# unit_module.net
KiCad netlist of a schematic drawn in EAGLE
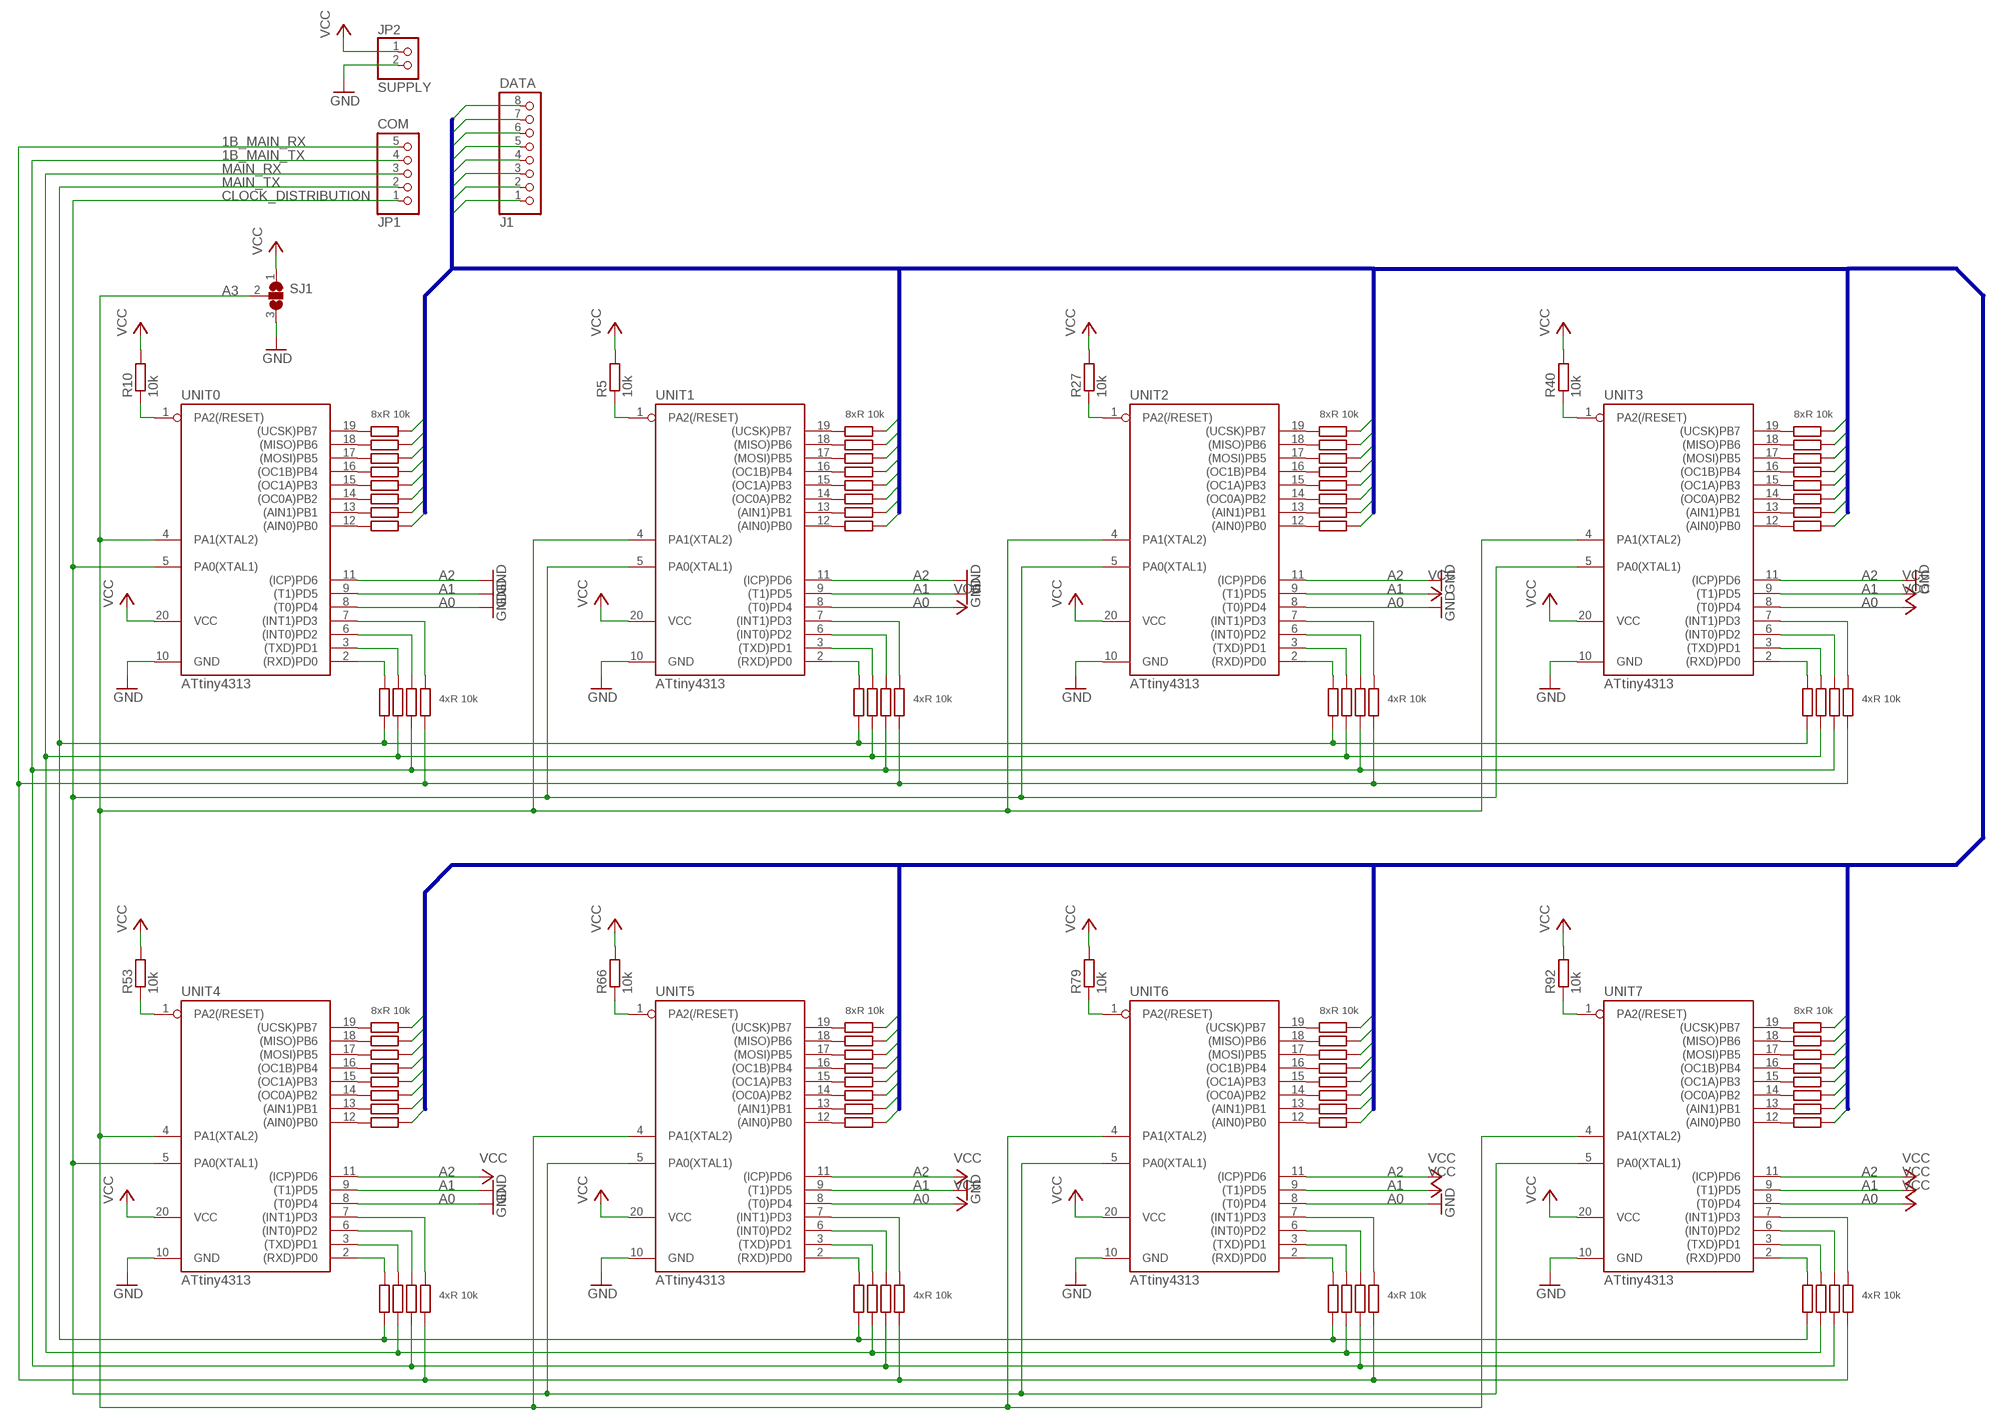
[diagram p0: schematic, sheet 1]

(export (version "E")
  (design (tool "Eeschema 10.0.6"))
  (components
    (comp (ref "J1")
      (value "DATA")
      (footprint "eagle-import:1X08")
      (libsource (lib "eagle-import") (part "PINHD-1X8"))
    )
    (comp (ref "JP1")
      (value "COM")
      (footprint "eagle-import:1X05")
      (libsource (lib "eagle-import") (part "PINHD-1X5"))
    )
    (comp (ref "JP2")
      (value "SUPPLY")
      (footprint "eagle-import:1X02")
      (libsource (lib "eagle-import") (part "PINHD-1X2"))
    )
    (comp (ref "R1")
      (value "10k")
      (footprint "eagle-import:R0603")
      (libsource (lib "eagle-import") (part "R-EU_R0603"))
    )
    (comp (ref "R2")
      (value "10k")
      (footprint "eagle-import:R0603")
      (libsource (lib "eagle-import") (part "R-EU_R0603"))
    )
    (comp (ref "R3")
      (value "10k")
      (footprint "eagle-import:R0603")
      (libsource (lib "eagle-import") (part "R-EU_R0603"))
    )
    (comp (ref "R4")
      (value "10k")
      (footprint "eagle-import:R0603")
      (libsource (lib "eagle-import") (part "R-EU_R0603"))
    )
    (comp (ref "R5")
      (value "10k")
      (footprint "eagle-import:R0603")
      (libsource (lib "eagle-import") (part "R-EU_R0603"))
    )
    (comp (ref "R6")
      (value "10k")
      (footprint "eagle-import:R0603")
      (libsource (lib "eagle-import") (part "R-EU_R0603"))
    )
    (comp (ref "R7")
      (value "10k")
      (footprint "eagle-import:R0603")
      (libsource (lib "eagle-import") (part "R-EU_R0603"))
    )
    (comp (ref "R8")
      (value "10k")
      (footprint "eagle-import:R0603")
      (libsource (lib "eagle-import") (part "R-EU_R0603"))
    )
    (comp (ref "R9")
      (value "10k")
      (footprint "eagle-import:R0603")
      (libsource (lib "eagle-import") (part "R-EU_R0603"))
    )
    (comp (ref "R10")
      (value "10k")
      (footprint "eagle-import:R0603")
      (libsource (lib "eagle-import") (part "R-EU_R0603"))
    )
    (comp (ref "R11")
      (value "10k")
      (footprint "eagle-import:R0603")
      (libsource (lib "eagle-import") (part "R-EU_R0603"))
    )
    (comp (ref "R12")
      (value "10k")
      (footprint "eagle-import:R0603")
      (libsource (lib "eagle-import") (part "R-EU_R0603"))
    )
    (comp (ref "R13")
      (value "10k")
      (footprint "eagle-import:R0603")
      (libsource (lib "eagle-import") (part "R-EU_R0603"))
    )
    (comp (ref "R14")
      (value "10k")
      (footprint "eagle-import:R0603")
      (libsource (lib "eagle-import") (part "R-EU_R0603"))
    )
    (comp (ref "R15")
      (value "10k")
      (footprint "eagle-import:R0603")
      (libsource (lib "eagle-import") (part "R-EU_R0603"))
    )
    (comp (ref "R16")
      (value "10k")
      (footprint "eagle-import:R0603")
      (libsource (lib "eagle-import") (part "R-EU_R0603"))
    )
    (comp (ref "R17")
      (value "10k")
      (footprint "eagle-import:R0603")
      (libsource (lib "eagle-import") (part "R-EU_R0603"))
    )
    (comp (ref "R18")
      (value "10k")
      (footprint "eagle-import:R0603")
      (libsource (lib "eagle-import") (part "R-EU_R0603"))
    )
    (comp (ref "R19")
      (value "10k")
      (footprint "eagle-import:R0603")
      (libsource (lib "eagle-import") (part "R-EU_R0603"))
    )
    (comp (ref "R20")
      (value "10k")
      (footprint "eagle-import:R0603")
      (libsource (lib "eagle-import") (part "R-EU_R0603"))
    )
    (comp (ref "R21")
      (value "10k")
      (footprint "eagle-import:R0603")
      (libsource (lib "eagle-import") (part "R-EU_R0603"))
    )
    (comp (ref "R22")
      (value "10k")
      (footprint "eagle-import:R0603")
      (libsource (lib "eagle-import") (part "R-EU_R0603"))
    )
    (comp (ref "R23")
      (value "10k")
      (footprint "eagle-import:R0603")
      (libsource (lib "eagle-import") (part "R-EU_R0603"))
    )
    (comp (ref "R24")
      (value "10k")
      (footprint "eagle-import:R0603")
      (libsource (lib "eagle-import") (part "R-EU_R0603"))
    )
    (comp (ref "R25")
      (value "10k")
      (footprint "eagle-import:R0603")
      (libsource (lib "eagle-import") (part "R-EU_R0603"))
    )
    (comp (ref "R26")
      (value "10k")
      (footprint "eagle-import:R0603")
      (libsource (lib "eagle-import") (part "R-EU_R0603"))
    )
    (comp (ref "R27")
      (value "10k")
      (footprint "eagle-import:R0603")
      (libsource (lib "eagle-import") (part "R-EU_R0603"))
    )
    (comp (ref "R28")
      (value "10k")
      (footprint "eagle-import:R0603")
      (libsource (lib "eagle-import") (part "R-EU_R0603"))
    )
    (comp (ref "R29")
      (value "10k")
      (footprint "eagle-import:R0603")
      (libsource (lib "eagle-import") (part "R-EU_R0603"))
    )
    (comp (ref "R30")
      (value "10k")
      (footprint "eagle-import:R0603")
      (libsource (lib "eagle-import") (part "R-EU_R0603"))
    )
    (comp (ref "R31")
      (value "10k")
      (footprint "eagle-import:R0603")
      (libsource (lib "eagle-import") (part "R-EU_R0603"))
    )
    (comp (ref "R32")
      (value "10k")
      (footprint "eagle-import:R0603")
      (libsource (lib "eagle-import") (part "R-EU_R0603"))
    )
    (comp (ref "R33")
      (value "10k")
      (footprint "eagle-import:R0603")
      (libsource (lib "eagle-import") (part "R-EU_R0603"))
    )
    (comp (ref "R34")
      (value "10k")
      (footprint "eagle-import:R0603")
      (libsource (lib "eagle-import") (part "R-EU_R0603"))
    )
    (comp (ref "R35")
      (value "10k")
      (footprint "eagle-import:R0603")
      (libsource (lib "eagle-import") (part "R-EU_R0603"))
    )
    (comp (ref "R36")
      (value "10k")
      (footprint "eagle-import:R0603")
      (libsource (lib "eagle-import") (part "R-EU_R0603"))
    )
    (comp (ref "R37")
      (value "10k")
      (footprint "eagle-import:R0603")
      (libsource (lib "eagle-import") (part "R-EU_R0603"))
    )
    (comp (ref "R38")
      (value "10k")
      (footprint "eagle-import:R0603")
      (libsource (lib "eagle-import") (part "R-EU_R0603"))
    )
    (comp (ref "R39")
      (value "10k")
      (footprint "eagle-import:R0603")
      (libsource (lib "eagle-import") (part "R-EU_R0603"))
    )
    (comp (ref "R40")
      (value "10k")
      (footprint "eagle-import:R0603")
      (libsource (lib "eagle-import") (part "R-EU_R0603"))
    )
    (comp (ref "R41")
      (value "10k")
      (footprint "eagle-import:R0603")
      (libsource (lib "eagle-import") (part "R-EU_R0603"))
    )
    (comp (ref "R42")
      (value "10k")
      (footprint "eagle-import:R0603")
      (libsource (lib "eagle-import") (part "R-EU_R0603"))
    )
    (comp (ref "R43")
      (value "10k")
      (footprint "eagle-import:R0603")
      (libsource (lib "eagle-import") (part "R-EU_R0603"))
    )
    (comp (ref "R44")
      (value "10k")
      (footprint "eagle-import:R0603")
      (libsource (lib "eagle-import") (part "R-EU_R0603"))
    )
    (comp (ref "R45")
      (value "10k")
      (footprint "eagle-import:R0603")
      (libsource (lib "eagle-import") (part "R-EU_R0603"))
    )
    (comp (ref "R46")
      (value "10k")
      (footprint "eagle-import:R0603")
      (libsource (lib "eagle-import") (part "R-EU_R0603"))
    )
    (comp (ref "R47")
      (value "10k")
      (footprint "eagle-import:R0603")
      (libsource (lib "eagle-import") (part "R-EU_R0603"))
    )
    (comp (ref "R48")
      (value "10k")
      (footprint "eagle-import:R0603")
      (libsource (lib "eagle-import") (part "R-EU_R0603"))
    )
    (comp (ref "R49")
      (value "10k")
      (footprint "eagle-import:R0603")
      (libsource (lib "eagle-import") (part "R-EU_R0603"))
    )
    (comp (ref "R50")
      (value "10k")
      (footprint "eagle-import:R0603")
      (libsource (lib "eagle-import") (part "R-EU_R0603"))
    )
    (comp (ref "R51")
      (value "10k")
      (footprint "eagle-import:R0603")
      (libsource (lib "eagle-import") (part "R-EU_R0603"))
    )
    (comp (ref "R52")
      (value "10k")
      (footprint "eagle-import:R0603")
      (libsource (lib "eagle-import") (part "R-EU_R0603"))
    )
    (comp (ref "R53")
      (value "10k")
      (footprint "eagle-import:R0603")
      (libsource (lib "eagle-import") (part "R-EU_R0603"))
    )
    (comp (ref "R54")
      (value "10k")
      (footprint "eagle-import:R0603")
      (libsource (lib "eagle-import") (part "R-EU_R0603"))
    )
    (comp (ref "R55")
      (value "10k")
      (footprint "eagle-import:R0603")
      (libsource (lib "eagle-import") (part "R-EU_R0603"))
    )
    (comp (ref "R56")
      (value "10k")
      (footprint "eagle-import:R0603")
      (libsource (lib "eagle-import") (part "R-EU_R0603"))
    )
    (comp (ref "R57")
      (value "10k")
      (footprint "eagle-import:R0603")
      (libsource (lib "eagle-import") (part "R-EU_R0603"))
    )
    (comp (ref "R58")
      (value "10k")
      (footprint "eagle-import:R0603")
      (libsource (lib "eagle-import") (part "R-EU_R0603"))
    )
    (comp (ref "R59")
      (value "10k")
      (footprint "eagle-import:R0603")
      (libsource (lib "eagle-import") (part "R-EU_R0603"))
    )
    (comp (ref "R60")
      (value "10k")
      (footprint "eagle-import:R0603")
      (libsource (lib "eagle-import") (part "R-EU_R0603"))
    )
    (comp (ref "R61")
      (value "10k")
      (footprint "eagle-import:R0603")
      (libsource (lib "eagle-import") (part "R-EU_R0603"))
    )
    (comp (ref "R62")
      (value "10k")
      (footprint "eagle-import:R0603")
      (libsource (lib "eagle-import") (part "R-EU_R0603"))
    )
    (comp (ref "R63")
      (value "10k")
      (footprint "eagle-import:R0603")
      (libsource (lib "eagle-import") (part "R-EU_R0603"))
    )
    (comp (ref "R64")
      (value "10k")
      (footprint "eagle-import:R0603")
      (libsource (lib "eagle-import") (part "R-EU_R0603"))
    )
    (comp (ref "R65")
      (value "10k")
      (footprint "eagle-import:R0603")
      (libsource (lib "eagle-import") (part "R-EU_R0603"))
    )
    (comp (ref "R66")
      (value "10k")
      (footprint "eagle-import:R0603")
      (libsource (lib "eagle-import") (part "R-EU_R0603"))
    )
    (comp (ref "R67")
      (value "10k")
      (footprint "eagle-import:R0603")
      (libsource (lib "eagle-import") (part "R-EU_R0603"))
    )
    (comp (ref "R68")
      (value "10k")
      (footprint "eagle-import:R0603")
      (libsource (lib "eagle-import") (part "R-EU_R0603"))
    )
    (comp (ref "R69")
      (value "10k")
      (footprint "eagle-import:R0603")
      (libsource (lib "eagle-import") (part "R-EU_R0603"))
    )
    (comp (ref "R70")
      (value "10k")
      (footprint "eagle-import:R0603")
      (libsource (lib "eagle-import") (part "R-EU_R0603"))
    )
    (comp (ref "R71")
      (value "10k")
      (footprint "eagle-import:R0603")
      (libsource (lib "eagle-import") (part "R-EU_R0603"))
    )
    (comp (ref "R72")
      (value "10k")
      (footprint "eagle-import:R0603")
      (libsource (lib "eagle-import") (part "R-EU_R0603"))
    )
    (comp (ref "R73")
      (value "10k")
      (footprint "eagle-import:R0603")
      (libsource (lib "eagle-import") (part "R-EU_R0603"))
    )
    (comp (ref "R74")
      (value "10k")
      (footprint "eagle-import:R0603")
      (libsource (lib "eagle-import") (part "R-EU_R0603"))
    )
    (comp (ref "R75")
      (value "10k")
      (footprint "eagle-import:R0603")
      (libsource (lib "eagle-import") (part "R-EU_R0603"))
    )
    (comp (ref "R76")
      (value "10k")
      (footprint "eagle-import:R0603")
      (libsource (lib "eagle-import") (part "R-EU_R0603"))
    )
    (comp (ref "R77")
      (value "10k")
      (footprint "eagle-import:R0603")
      (libsource (lib "eagle-import") (part "R-EU_R0603"))
    )
    (comp (ref "R78")
      (value "10k")
      (footprint "eagle-import:R0603")
      (libsource (lib "eagle-import") (part "R-EU_R0603"))
    )
    (comp (ref "R79")
      (value "10k")
      (footprint "eagle-import:R0603")
      (libsource (lib "eagle-import") (part "R-EU_R0603"))
    )
    (comp (ref "R80")
      (value "10k")
      (footprint "eagle-import:R0603")
      (libsource (lib "eagle-import") (part "R-EU_R0603"))
    )
    (comp (ref "R81")
      (value "10k")
      (footprint "eagle-import:R0603")
      (libsource (lib "eagle-import") (part "R-EU_R0603"))
    )
    (comp (ref "R82")
      (value "10k")
      (footprint "eagle-import:R0603")
      (libsource (lib "eagle-import") (part "R-EU_R0603"))
    )
    (comp (ref "R83")
      (value "10k")
      (footprint "eagle-import:R0603")
      (libsource (lib "eagle-import") (part "R-EU_R0603"))
    )
    (comp (ref "R84")
      (value "10k")
      (footprint "eagle-import:R0603")
      (libsource (lib "eagle-import") (part "R-EU_R0603"))
    )
    (comp (ref "R85")
      (value "10k")
      (footprint "eagle-import:R0603")
      (libsource (lib "eagle-import") (part "R-EU_R0603"))
    )
    (comp (ref "R86")
      (value "10k")
      (footprint "eagle-import:R0603")
      (libsource (lib "eagle-import") (part "R-EU_R0603"))
    )
    (comp (ref "R87")
      (value "10k")
      (footprint "eagle-import:R0603")
      (libsource (lib "eagle-import") (part "R-EU_R0603"))
    )
    (comp (ref "R88")
      (value "10k")
      (footprint "eagle-import:R0603")
      (libsource (lib "eagle-import") (part "R-EU_R0603"))
    )
    (comp (ref "R89")
      (value "10k")
      (footprint "eagle-import:R0603")
      (libsource (lib "eagle-import") (part "R-EU_R0603"))
    )
    (comp (ref "R90")
      (value "10k")
      (footprint "eagle-import:R0603")
      (libsource (lib "eagle-import") (part "R-EU_R0603"))
    )
    (comp (ref "R91")
      (value "10k")
      (footprint "eagle-import:R0603")
      (libsource (lib "eagle-import") (part "R-EU_R0603"))
    )
    (comp (ref "R92")
      (value "10k")
      (footprint "eagle-import:R0603")
      (libsource (lib "eagle-import") (part "R-EU_R0603"))
    )
    (comp (ref "R93")
      (value "10k")
      (footprint "eagle-import:R0603")
      (libsource (lib "eagle-import") (part "R-EU_R0603"))
    )
    (comp (ref "R94")
      (value "10k")
      (footprint "eagle-import:R0603")
      (libsource (lib "eagle-import") (part "R-EU_R0603"))
    )
    (comp (ref "R95")
      (value "10k")
      (footprint "eagle-import:R0603")
      (libsource (lib "eagle-import") (part "R-EU_R0603"))
    )
    (comp (ref "R96")
      (value "10k")
      (footprint "eagle-import:R0603")
      (libsource (lib "eagle-import") (part "R-EU_R0603"))
    )
    (comp (ref "R97")
      (value "10k")
      (footprint "eagle-import:R0603")
      (libsource (lib "eagle-import") (part "R-EU_R0603"))
    )
    (comp (ref "R98")
      (value "10k")
      (footprint "eagle-import:R0603")
      (libsource (lib "eagle-import") (part "R-EU_R0603"))
    )
    (comp (ref "R99")
      (value "10k")
      (footprint "eagle-import:R0603")
      (libsource (lib "eagle-import") (part "R-EU_R0603"))
    )
    (comp (ref "R100")
      (value "10k")
      (footprint "eagle-import:R0603")
      (libsource (lib "eagle-import") (part "R-EU_R0603"))
    )
    (comp (ref "R101")
      (value "10k")
      (footprint "eagle-import:R0603")
      (libsource (lib "eagle-import") (part "R-EU_R0603"))
    )
    (comp (ref "R102")
      (value "10k")
      (footprint "eagle-import:R0603")
      (libsource (lib "eagle-import") (part "R-EU_R0603"))
    )
    (comp (ref "R103")
      (value "10k")
      (footprint "eagle-import:R0603")
      (libsource (lib "eagle-import") (part "R-EU_R0603"))
    )
    (comp (ref "R104")
      (value "10k")
      (footprint "eagle-import:R0603")
      (libsource (lib "eagle-import") (part "R-EU_R0603"))
    )
    (comp (ref "SJ1")
      (value "SJ2W")
      (footprint "eagle-import:SJ_2")
      (libsource (lib "eagle-import") (part "SJ2W"))
    )
    (comp (ref "UNIT0")
      (value "ATtiny4313")
      (footprint "eagle-import:DIL20")
      (libsource (lib "eagle-import") (part "TINY2313-P"))
    )
    (comp (ref "UNIT1")
      (value "ATtiny4313")
      (footprint "eagle-import:DIL20")
      (libsource (lib "eagle-import") (part "TINY2313-P"))
    )
    (comp (ref "UNIT2")
      (value "ATtiny4313")
      (footprint "eagle-import:DIL20")
      (libsource (lib "eagle-import") (part "TINY2313-P"))
    )
    (comp (ref "UNIT3")
      (value "ATtiny4313")
      (footprint "eagle-import:DIL20")
      (libsource (lib "eagle-import") (part "TINY2313-P"))
    )
    (comp (ref "UNIT4")
      (value "ATtiny4313")
      (footprint "eagle-import:DIL20")
      (libsource (lib "eagle-import") (part "TINY2313-P"))
    )
    (comp (ref "UNIT5")
      (value "ATtiny4313")
      (footprint "eagle-import:DIL20")
      (libsource (lib "eagle-import") (part "TINY2313-P"))
    )
    (comp (ref "UNIT6")
      (value "ATtiny4313")
      (footprint "eagle-import:DIL20")
      (libsource (lib "eagle-import") (part "TINY2313-P"))
    )
    (comp (ref "UNIT7")
      (value "ATtiny4313")
      (footprint "eagle-import:DIL20")
      (libsource (lib "eagle-import") (part "TINY2313-P"))
    )
  )
  (nets
    (net (code "1") (name "/1B_MAIN_RX") (class "Default")
      (node (ref "JP1") (pin "5") (pinfunction "5_5") (pintype "passive"))
      (node (ref "R104") (pin "2") (pinfunction "2_2") (pintype "passive"))
      (node (ref "R26") (pin "2") (pinfunction "2_2") (pintype "passive"))
      (node (ref "R39") (pin "2") (pinfunction "2_2") (pintype "passive"))
      (node (ref "R4") (pin "2") (pinfunction "2_2") (pintype "passive"))
      (node (ref "R52") (pin "2") (pinfunction "2_2") (pintype "passive"))
      (node (ref "R65") (pin "2") (pinfunction "2_2") (pintype "passive"))
      (node (ref "R78") (pin "2") (pinfunction "2_2") (pintype "passive"))
      (node (ref "R91") (pin "2") (pinfunction "2_2") (pintype "passive"))
    )
    (net (code "2") (name "/1B_MAIN_TX") (class "Default")
      (node (ref "JP1") (pin "4") (pinfunction "4_4") (pintype "passive"))
      (node (ref "R103") (pin "2") (pinfunction "2_2") (pintype "passive"))
      (node (ref "R25") (pin "2") (pinfunction "2_2") (pintype "passive"))
      (node (ref "R3") (pin "2") (pinfunction "2_2") (pintype "passive"))
      (node (ref "R38") (pin "2") (pinfunction "2_2") (pintype "passive"))
      (node (ref "R51") (pin "2") (pinfunction "2_2") (pintype "passive"))
      (node (ref "R64") (pin "2") (pinfunction "2_2") (pintype "passive"))
      (node (ref "R77") (pin "2") (pinfunction "2_2") (pintype "passive"))
      (node (ref "R90") (pin "2") (pinfunction "2_2") (pintype "passive"))
    )
    (net (code "3") (name "/A3") (class "Default")
      (node (ref "SJ1") (pin "2") (pinfunction "2_2") (pintype "passive"))
      (node (ref "UNIT0") (pin "4") (pinfunction "PA1(XTAL2)_4") (pintype "bidirectional"))
      (node (ref "UNIT1") (pin "4") (pinfunction "PA1(XTAL2)_4") (pintype "bidirectional"))
      (node (ref "UNIT2") (pin "4") (pinfunction "PA1(XTAL2)_4") (pintype "bidirectional"))
      (node (ref "UNIT3") (pin "4") (pinfunction "PA1(XTAL2)_4") (pintype "bidirectional"))
      (node (ref "UNIT4") (pin "4") (pinfunction "PA1(XTAL2)_4") (pintype "bidirectional"))
      (node (ref "UNIT5") (pin "4") (pinfunction "PA1(XTAL2)_4") (pintype "bidirectional"))
      (node (ref "UNIT6") (pin "4") (pinfunction "PA1(XTAL2)_4") (pintype "bidirectional"))
      (node (ref "UNIT7") (pin "4") (pinfunction "PA1(XTAL2)_4") (pintype "bidirectional"))
    )
    (net (code "4") (name "/CLOCK_DISTRIBUTION") (class "Default")
      (node (ref "JP1") (pin "1") (pinfunction "1_1") (pintype "passive"))
      (node (ref "UNIT0") (pin "5") (pinfunction "PA0(XTAL1)_5") (pintype "bidirectional"))
      (node (ref "UNIT1") (pin "5") (pinfunction "PA0(XTAL1)_5") (pintype "bidirectional"))
      (node (ref "UNIT2") (pin "5") (pinfunction "PA0(XTAL1)_5") (pintype "bidirectional"))
      (node (ref "UNIT3") (pin "5") (pinfunction "PA0(XTAL1)_5") (pintype "bidirectional"))
      (node (ref "UNIT4") (pin "5") (pinfunction "PA0(XTAL1)_5") (pintype "bidirectional"))
      (node (ref "UNIT5") (pin "5") (pinfunction "PA0(XTAL1)_5") (pintype "bidirectional"))
      (node (ref "UNIT6") (pin "5") (pinfunction "PA0(XTAL1)_5") (pintype "bidirectional"))
      (node (ref "UNIT7") (pin "5") (pinfunction "PA0(XTAL1)_5") (pintype "bidirectional"))
    )
    (net (code "5") (name "/DATA0") (class "Default")
      (node (ref "J1") (pin "1") (pinfunction "1_1") (pintype "passive"))
      (node (ref "R100") (pin "1") (pinfunction "1_1") (pintype "passive"))
      (node (ref "R19") (pin "1") (pinfunction "1_1") (pintype "passive"))
      (node (ref "R22") (pin "1") (pinfunction "1_1") (pintype "passive"))
      (node (ref "R35") (pin "1") (pinfunction "1_1") (pintype "passive"))
      (node (ref "R48") (pin "1") (pinfunction "1_1") (pintype "passive"))
      (node (ref "R61") (pin "1") (pinfunction "1_1") (pintype "passive"))
      (node (ref "R74") (pin "1") (pinfunction "1_1") (pintype "passive"))
      (node (ref "R87") (pin "1") (pinfunction "1_1") (pintype "passive"))
    )
    (net (code "6") (name "/DATA1") (class "Default")
      (node (ref "J1") (pin "2") (pinfunction "2_2") (pintype "passive"))
      (node (ref "R18") (pin "1") (pinfunction "1_1") (pintype "passive"))
      (node (ref "R21") (pin "1") (pinfunction "1_1") (pintype "passive"))
      (node (ref "R34") (pin "1") (pinfunction "1_1") (pintype "passive"))
      (node (ref "R47") (pin "1") (pinfunction "1_1") (pintype "passive"))
      (node (ref "R60") (pin "1") (pinfunction "1_1") (pintype "passive"))
      (node (ref "R73") (pin "1") (pinfunction "1_1") (pintype "passive"))
      (node (ref "R86") (pin "1") (pinfunction "1_1") (pintype "passive"))
      (node (ref "R99") (pin "1") (pinfunction "1_1") (pintype "passive"))
    )
    (net (code "7") (name "/DATA2") (class "Default")
      (node (ref "J1") (pin "3") (pinfunction "3_3") (pintype "passive"))
      (node (ref "R17") (pin "1") (pinfunction "1_1") (pintype "passive"))
      (node (ref "R20") (pin "1") (pinfunction "1_1") (pintype "passive"))
      (node (ref "R33") (pin "1") (pinfunction "1_1") (pintype "passive"))
      (node (ref "R46") (pin "1") (pinfunction "1_1") (pintype "passive"))
      (node (ref "R59") (pin "1") (pinfunction "1_1") (pintype "passive"))
      (node (ref "R72") (pin "1") (pinfunction "1_1") (pintype "passive"))
      (node (ref "R85") (pin "1") (pinfunction "1_1") (pintype "passive"))
      (node (ref "R98") (pin "1") (pinfunction "1_1") (pintype "passive"))
    )
    (net (code "8") (name "/DATA3") (class "Default")
      (node (ref "J1") (pin "4") (pinfunction "4_4") (pintype "passive"))
      (node (ref "R11") (pin "1") (pinfunction "1_1") (pintype "passive"))
      (node (ref "R16") (pin "1") (pinfunction "1_1") (pintype "passive"))
      (node (ref "R32") (pin "1") (pinfunction "1_1") (pintype "passive"))
      (node (ref "R45") (pin "1") (pinfunction "1_1") (pintype "passive"))
      (node (ref "R58") (pin "1") (pinfunction "1_1") (pintype "passive"))
      (node (ref "R71") (pin "1") (pinfunction "1_1") (pintype "passive"))
      (node (ref "R84") (pin "1") (pinfunction "1_1") (pintype "passive"))
      (node (ref "R97") (pin "1") (pinfunction "1_1") (pintype "passive"))
    )
    (net (code "9") (name "/DATA4") (class "Default")
      (node (ref "J1") (pin "5") (pinfunction "5_5") (pintype "passive"))
      (node (ref "R15") (pin "1") (pinfunction "1_1") (pintype "passive"))
      (node (ref "R31") (pin "1") (pinfunction "1_1") (pintype "passive"))
      (node (ref "R44") (pin "1") (pinfunction "1_1") (pintype "passive"))
      (node (ref "R57") (pin "1") (pinfunction "1_1") (pintype "passive"))
      (node (ref "R70") (pin "1") (pinfunction "1_1") (pintype "passive"))
      (node (ref "R83") (pin "1") (pinfunction "1_1") (pintype "passive"))
      (node (ref "R9") (pin "1") (pinfunction "1_1") (pintype "passive"))
      (node (ref "R96") (pin "1") (pinfunction "1_1") (pintype "passive"))
    )
    (net (code "10") (name "/DATA5") (class "Default")
      (node (ref "J1") (pin "6") (pinfunction "6_6") (pintype "passive"))
      (node (ref "R14") (pin "1") (pinfunction "1_1") (pintype "passive"))
      (node (ref "R30") (pin "1") (pinfunction "1_1") (pintype "passive"))
      (node (ref "R43") (pin "1") (pinfunction "1_1") (pintype "passive"))
      (node (ref "R56") (pin "1") (pinfunction "1_1") (pintype "passive"))
      (node (ref "R69") (pin "1") (pinfunction "1_1") (pintype "passive"))
      (node (ref "R8") (pin "1") (pinfunction "1_1") (pintype "passive"))
      (node (ref "R82") (pin "1") (pinfunction "1_1") (pintype "passive"))
      (node (ref "R95") (pin "1") (pinfunction "1_1") (pintype "passive"))
    )
    (net (code "11") (name "/DATA6") (class "Default")
      (node (ref "J1") (pin "7") (pinfunction "7_7") (pintype "passive"))
      (node (ref "R13") (pin "1") (pinfunction "1_1") (pintype "passive"))
      (node (ref "R29") (pin "1") (pinfunction "1_1") (pintype "passive"))
      (node (ref "R42") (pin "1") (pinfunction "1_1") (pintype "passive"))
      (node (ref "R55") (pin "1") (pinfunction "1_1") (pintype "passive"))
      (node (ref "R68") (pin "1") (pinfunction "1_1") (pintype "passive"))
      (node (ref "R7") (pin "1") (pinfunction "1_1") (pintype "passive"))
      (node (ref "R81") (pin "1") (pinfunction "1_1") (pintype "passive"))
      (node (ref "R94") (pin "1") (pinfunction "1_1") (pintype "passive"))
    )
    (net (code "12") (name "/DATA7") (class "Default")
      (node (ref "J1") (pin "8") (pinfunction "8_8") (pintype "passive"))
      (node (ref "R12") (pin "1") (pinfunction "1_1") (pintype "passive"))
      (node (ref "R28") (pin "1") (pinfunction "1_1") (pintype "passive"))
      (node (ref "R41") (pin "1") (pinfunction "1_1") (pintype "passive"))
      (node (ref "R54") (pin "1") (pinfunction "1_1") (pintype "passive"))
      (node (ref "R6") (pin "1") (pinfunction "1_1") (pintype "passive"))
      (node (ref "R67") (pin "1") (pinfunction "1_1") (pintype "passive"))
      (node (ref "R80") (pin "1") (pinfunction "1_1") (pintype "passive"))
      (node (ref "R93") (pin "1") (pinfunction "1_1") (pintype "passive"))
    )
    (net (code "13") (name "/MAIN_RX") (class "Default")
      (node (ref "JP1") (pin "3") (pinfunction "3_3") (pintype "passive"))
      (node (ref "R102") (pin "2") (pinfunction "2_2") (pintype "passive"))
      (node (ref "R2") (pin "2") (pinfunction "2_2") (pintype "passive"))
      (node (ref "R24") (pin "2") (pinfunction "2_2") (pintype "passive"))
      (node (ref "R37") (pin "2") (pinfunction "2_2") (pintype "passive"))
      (node (ref "R50") (pin "2") (pinfunction "2_2") (pintype "passive"))
      (node (ref "R63") (pin "2") (pinfunction "2_2") (pintype "passive"))
      (node (ref "R76") (pin "2") (pinfunction "2_2") (pintype "passive"))
      (node (ref "R89") (pin "2") (pinfunction "2_2") (pintype "passive"))
    )
    (net (code "14") (name "/MAIN_TX") (class "Default")
      (node (ref "JP1") (pin "2") (pinfunction "2_2") (pintype "passive"))
      (node (ref "R1") (pin "2") (pinfunction "2_2") (pintype "passive"))
      (node (ref "R101") (pin "2") (pinfunction "2_2") (pintype "passive"))
      (node (ref "R23") (pin "2") (pinfunction "2_2") (pintype "passive"))
      (node (ref "R36") (pin "2") (pinfunction "2_2") (pintype "passive"))
      (node (ref "R49") (pin "2") (pinfunction "2_2") (pintype "passive"))
      (node (ref "R62") (pin "2") (pinfunction "2_2") (pintype "passive"))
      (node (ref "R75") (pin "2") (pinfunction "2_2") (pintype "passive"))
      (node (ref "R88") (pin "2") (pinfunction "2_2") (pintype "passive"))
    )
    (net (code "15") (name "GND") (class "Default")
      (node (ref "JP2") (pin "2") (pinfunction "2_2") (pintype "passive"))
      (node (ref "SJ1") (pin "3") (pinfunction "3_3") (pintype "passive"))
      (node (ref "UNIT0") (pin "10") (pinfunction "GND_10") (pintype "power_in"))
      (node (ref "UNIT0") (pin "11") (pinfunction "(ICP)PD6_11") (pintype "bidirectional"))
      (node (ref "UNIT0") (pin "8") (pinfunction "(T0)PD4_8") (pintype "bidirectional"))
      (node (ref "UNIT0") (pin "9") (pinfunction "(T1)PD5_9") (pintype "bidirectional"))
      (node (ref "UNIT1") (pin "10") (pinfunction "GND_10") (pintype "power_in"))
      (node (ref "UNIT1") (pin "11") (pinfunction "(ICP)PD6_11") (pintype "bidirectional"))
      (node (ref "UNIT1") (pin "9") (pinfunction "(T1)PD5_9") (pintype "bidirectional"))
      (node (ref "UNIT2") (pin "10") (pinfunction "GND_10") (pintype "power_in"))
      (node (ref "UNIT2") (pin "11") (pinfunction "(ICP)PD6_11") (pintype "bidirectional"))
      (node (ref "UNIT2") (pin "8") (pinfunction "(T0)PD4_8") (pintype "bidirectional"))
      (node (ref "UNIT3") (pin "10") (pinfunction "GND_10") (pintype "power_in"))
      (node (ref "UNIT3") (pin "11") (pinfunction "(ICP)PD6_11") (pintype "bidirectional"))
      (node (ref "UNIT4") (pin "10") (pinfunction "GND_10") (pintype "power_in"))
      (node (ref "UNIT4") (pin "8") (pinfunction "(T0)PD4_8") (pintype "bidirectional"))
      (node (ref "UNIT4") (pin "9") (pinfunction "(T1)PD5_9") (pintype "bidirectional"))
      (node (ref "UNIT5") (pin "10") (pinfunction "GND_10") (pintype "power_in"))
      (node (ref "UNIT5") (pin "9") (pinfunction "(T1)PD5_9") (pintype "bidirectional"))
      (node (ref "UNIT6") (pin "10") (pinfunction "GND_10") (pintype "power_in"))
      (node (ref "UNIT6") (pin "8") (pinfunction "(T0)PD4_8") (pintype "bidirectional"))
      (node (ref "UNIT7") (pin "10") (pinfunction "GND_10") (pintype "power_in"))
    )
    (net (code "16") (name "Net-(UNIT0-(AIN0)PB0)") (class "Default")
      (node (ref "R19") (pin "2") (pinfunction "2_2") (pintype "passive"))
      (node (ref "UNIT0") (pin "12") (pinfunction "(AIN0)PB0_12") (pintype "bidirectional"))
    )
    (net (code "17") (name "Net-(UNIT0-(AIN1)PB1)") (class "Default")
      (node (ref "R18") (pin "2") (pinfunction "2_2") (pintype "passive"))
      (node (ref "UNIT0") (pin "13") (pinfunction "(AIN1)PB1_13") (pintype "bidirectional"))
    )
    (net (code "18") (name "Net-(UNIT0-(INT0)PD2)") (class "Default")
      (node (ref "R3") (pin "1") (pinfunction "1_1") (pintype "passive"))
      (node (ref "UNIT0") (pin "6") (pinfunction "(INT0)PD2_6") (pintype "bidirectional"))
    )
    (net (code "19") (name "Net-(UNIT0-(INT1)PD3)") (class "Default")
      (node (ref "R4") (pin "1") (pinfunction "1_1") (pintype "passive"))
      (node (ref "UNIT0") (pin "7") (pinfunction "(INT1)PD3_7") (pintype "bidirectional"))
    )
    (net (code "20") (name "Net-(UNIT0-(MISO)PB6)") (class "Default")
      (node (ref "R13") (pin "2") (pinfunction "2_2") (pintype "passive"))
      (node (ref "UNIT0") (pin "18") (pinfunction "(MISO)PB6_18") (pintype "bidirectional"))
    )
    (net (code "21") (name "Net-(UNIT0-(MOSI)PB5)") (class "Default")
      (node (ref "R14") (pin "2") (pinfunction "2_2") (pintype "passive"))
      (node (ref "UNIT0") (pin "17") (pinfunction "(MOSI)PB5_17") (pintype "bidirectional"))
    )
    (net (code "22") (name "Net-(UNIT0-(OC0A)PB2)") (class "Default")
      (node (ref "R17") (pin "2") (pinfunction "2_2") (pintype "passive"))
      (node (ref "UNIT0") (pin "14") (pinfunction "(OC0A)PB2_14") (pintype "bidirectional"))
    )
    (net (code "23") (name "Net-(UNIT0-(OC1A)PB3)") (class "Default")
      (node (ref "R16") (pin "2") (pinfunction "2_2") (pintype "passive"))
      (node (ref "UNIT0") (pin "15") (pinfunction "(OC1A)PB3_15") (pintype "bidirectional"))
    )
    (net (code "24") (name "Net-(UNIT0-(OC1B)PB4)") (class "Default")
      (node (ref "R15") (pin "2") (pinfunction "2_2") (pintype "passive"))
      (node (ref "UNIT0") (pin "16") (pinfunction "(OC1B)PB4_16") (pintype "bidirectional"))
    )
    (net (code "25") (name "Net-(UNIT0-(RXD)PD0)") (class "Default")
      (node (ref "R1") (pin "1") (pinfunction "1_1") (pintype "passive"))
      (node (ref "UNIT0") (pin "2") (pinfunction "(RXD)PD0_2") (pintype "bidirectional"))
    )
    (net (code "26") (name "Net-(UNIT0-(TXD)PD1)") (class "Default")
      (node (ref "R2") (pin "1") (pinfunction "1_1") (pintype "passive"))
      (node (ref "UNIT0") (pin "3") (pinfunction "(TXD)PD1_3") (pintype "bidirectional"))
    )
    (net (code "27") (name "Net-(UNIT0-(UCSK)PB7)") (class "Default")
      (node (ref "R12") (pin "2") (pinfunction "2_2") (pintype "passive"))
      (node (ref "UNIT0") (pin "19") (pinfunction "(UCSK)PB7_19") (pintype "bidirectional"))
    )
    (net (code "28") (name "Net-(UNIT0-PA2({slash}RESET))") (class "Default")
      (node (ref "R10") (pin "1") (pinfunction "1_1") (pintype "passive"))
      (node (ref "UNIT0") (pin "1") (pinfunction "PA2(/RESET)_1") (pintype "input"))
    )
    (net (code "29") (name "Net-(UNIT1-(AIN0)PB0)") (class "Default")
      (node (ref "R22") (pin "2") (pinfunction "2_2") (pintype "passive"))
      (node (ref "UNIT1") (pin "12") (pinfunction "(AIN0)PB0_12") (pintype "bidirectional"))
    )
    (net (code "30") (name "Net-(UNIT1-(AIN1)PB1)") (class "Default")
      (node (ref "R21") (pin "2") (pinfunction "2_2") (pintype "passive"))
      (node (ref "UNIT1") (pin "13") (pinfunction "(AIN1)PB1_13") (pintype "bidirectional"))
    )
    (net (code "31") (name "Net-(UNIT1-(INT0)PD2)") (class "Default")
      (node (ref "R25") (pin "1") (pinfunction "1_1") (pintype "passive"))
      (node (ref "UNIT1") (pin "6") (pinfunction "(INT0)PD2_6") (pintype "bidirectional"))
    )
    (net (code "32") (name "Net-(UNIT1-(INT1)PD3)") (class "Default")
      (node (ref "R26") (pin "1") (pinfunction "1_1") (pintype "passive"))
      (node (ref "UNIT1") (pin "7") (pinfunction "(INT1)PD3_7") (pintype "bidirectional"))
    )
    (net (code "33") (name "Net-(UNIT1-(MISO)PB6)") (class "Default")
      (node (ref "R7") (pin "2") (pinfunction "2_2") (pintype "passive"))
      (node (ref "UNIT1") (pin "18") (pinfunction "(MISO)PB6_18") (pintype "bidirectional"))
    )
    (net (code "34") (name "Net-(UNIT1-(MOSI)PB5)") (class "Default")
      (node (ref "R8") (pin "2") (pinfunction "2_2") (pintype "passive"))
      (node (ref "UNIT1") (pin "17") (pinfunction "(MOSI)PB5_17") (pintype "bidirectional"))
    )
    (net (code "35") (name "Net-(UNIT1-(OC0A)PB2)") (class "Default")
      (node (ref "R20") (pin "2") (pinfunction "2_2") (pintype "passive"))
      (node (ref "UNIT1") (pin "14") (pinfunction "(OC0A)PB2_14") (pintype "bidirectional"))
    )
    (net (code "36") (name "Net-(UNIT1-(OC1A)PB3)") (class "Default")
      (node (ref "R11") (pin "2") (pinfunction "2_2") (pintype "passive"))
      (node (ref "UNIT1") (pin "15") (pinfunction "(OC1A)PB3_15") (pintype "bidirectional"))
    )
    (net (code "37") (name "Net-(UNIT1-(OC1B)PB4)") (class "Default")
      (node (ref "R9") (pin "2") (pinfunction "2_2") (pintype "passive"))
      (node (ref "UNIT1") (pin "16") (pinfunction "(OC1B)PB4_16") (pintype "bidirectional"))
    )
    (net (code "38") (name "Net-(UNIT1-(RXD)PD0)") (class "Default")
      (node (ref "R23") (pin "1") (pinfunction "1_1") (pintype "passive"))
      (node (ref "UNIT1") (pin "2") (pinfunction "(RXD)PD0_2") (pintype "bidirectional"))
    )
    (net (code "39") (name "Net-(UNIT1-(TXD)PD1)") (class "Default")
      (node (ref "R24") (pin "1") (pinfunction "1_1") (pintype "passive"))
      (node (ref "UNIT1") (pin "3") (pinfunction "(TXD)PD1_3") (pintype "bidirectional"))
    )
    (net (code "40") (name "Net-(UNIT1-(UCSK)PB7)") (class "Default")
      (node (ref "R6") (pin "2") (pinfunction "2_2") (pintype "passive"))
      (node (ref "UNIT1") (pin "19") (pinfunction "(UCSK)PB7_19") (pintype "bidirectional"))
    )
    (net (code "41") (name "Net-(UNIT1-PA2({slash}RESET))") (class "Default")
      (node (ref "R5") (pin "1") (pinfunction "1_1") (pintype "passive"))
      (node (ref "UNIT1") (pin "1") (pinfunction "PA2(/RESET)_1") (pintype "input"))
    )
    (net (code "42") (name "Net-(UNIT2-(AIN0)PB0)") (class "Default")
      (node (ref "R35") (pin "2") (pinfunction "2_2") (pintype "passive"))
      (node (ref "UNIT2") (pin "12") (pinfunction "(AIN0)PB0_12") (pintype "bidirectional"))
    )
    (net (code "43") (name "Net-(UNIT2-(AIN1)PB1)") (class "Default")
      (node (ref "R34") (pin "2") (pinfunction "2_2") (pintype "passive"))
      (node (ref "UNIT2") (pin "13") (pinfunction "(AIN1)PB1_13") (pintype "bidirectional"))
    )
    (net (code "44") (name "Net-(UNIT2-(INT0)PD2)") (class "Default")
      (node (ref "R38") (pin "1") (pinfunction "1_1") (pintype "passive"))
      (node (ref "UNIT2") (pin "6") (pinfunction "(INT0)PD2_6") (pintype "bidirectional"))
    )
    (net (code "45") (name "Net-(UNIT2-(INT1)PD3)") (class "Default")
      (node (ref "R39") (pin "1") (pinfunction "1_1") (pintype "passive"))
      (node (ref "UNIT2") (pin "7") (pinfunction "(INT1)PD3_7") (pintype "bidirectional"))
    )
    (net (code "46") (name "Net-(UNIT2-(MISO)PB6)") (class "Default")
      (node (ref "R29") (pin "2") (pinfunction "2_2") (pintype "passive"))
      (node (ref "UNIT2") (pin "18") (pinfunction "(MISO)PB6_18") (pintype "bidirectional"))
    )
    (net (code "47") (name "Net-(UNIT2-(MOSI)PB5)") (class "Default")
      (node (ref "R30") (pin "2") (pinfunction "2_2") (pintype "passive"))
      (node (ref "UNIT2") (pin "17") (pinfunction "(MOSI)PB5_17") (pintype "bidirectional"))
    )
    (net (code "48") (name "Net-(UNIT2-(OC0A)PB2)") (class "Default")
      (node (ref "R33") (pin "2") (pinfunction "2_2") (pintype "passive"))
      (node (ref "UNIT2") (pin "14") (pinfunction "(OC0A)PB2_14") (pintype "bidirectional"))
    )
    (net (code "49") (name "Net-(UNIT2-(OC1A)PB3)") (class "Default")
      (node (ref "R32") (pin "2") (pinfunction "2_2") (pintype "passive"))
      (node (ref "UNIT2") (pin "15") (pinfunction "(OC1A)PB3_15") (pintype "bidirectional"))
    )
    (net (code "50") (name "Net-(UNIT2-(OC1B)PB4)") (class "Default")
      (node (ref "R31") (pin "2") (pinfunction "2_2") (pintype "passive"))
      (node (ref "UNIT2") (pin "16") (pinfunction "(OC1B)PB4_16") (pintype "bidirectional"))
    )
    (net (code "51") (name "Net-(UNIT2-(RXD)PD0)") (class "Default")
      (node (ref "R36") (pin "1") (pinfunction "1_1") (pintype "passive"))
      (node (ref "UNIT2") (pin "2") (pinfunction "(RXD)PD0_2") (pintype "bidirectional"))
    )
    (net (code "52") (name "Net-(UNIT2-(TXD)PD1)") (class "Default")
      (node (ref "R37") (pin "1") (pinfunction "1_1") (pintype "passive"))
      (node (ref "UNIT2") (pin "3") (pinfunction "(TXD)PD1_3") (pintype "bidirectional"))
    )
    (net (code "53") (name "Net-(UNIT2-(UCSK)PB7)") (class "Default")
      (node (ref "R28") (pin "2") (pinfunction "2_2") (pintype "passive"))
      (node (ref "UNIT2") (pin "19") (pinfunction "(UCSK)PB7_19") (pintype "bidirectional"))
    )
    (net (code "54") (name "Net-(UNIT2-PA2({slash}RESET))") (class "Default")
      (node (ref "R27") (pin "1") (pinfunction "1_1") (pintype "passive"))
      (node (ref "UNIT2") (pin "1") (pinfunction "PA2(/RESET)_1") (pintype "input"))
    )
    (net (code "55") (name "Net-(UNIT3-(AIN0)PB0)") (class "Default")
      (node (ref "R48") (pin "2") (pinfunction "2_2") (pintype "passive"))
      (node (ref "UNIT3") (pin "12") (pinfunction "(AIN0)PB0_12") (pintype "bidirectional"))
    )
    (net (code "56") (name "Net-(UNIT3-(AIN1)PB1)") (class "Default")
      (node (ref "R47") (pin "2") (pinfunction "2_2") (pintype "passive"))
      (node (ref "UNIT3") (pin "13") (pinfunction "(AIN1)PB1_13") (pintype "bidirectional"))
    )
    (net (code "57") (name "Net-(UNIT3-(INT0)PD2)") (class "Default")
      (node (ref "R51") (pin "1") (pinfunction "1_1") (pintype "passive"))
      (node (ref "UNIT3") (pin "6") (pinfunction "(INT0)PD2_6") (pintype "bidirectional"))
    )
    (net (code "58") (name "Net-(UNIT3-(INT1)PD3)") (class "Default")
      (node (ref "R52") (pin "1") (pinfunction "1_1") (pintype "passive"))
      (node (ref "UNIT3") (pin "7") (pinfunction "(INT1)PD3_7") (pintype "bidirectional"))
    )
    (net (code "59") (name "Net-(UNIT3-(MISO)PB6)") (class "Default")
      (node (ref "R42") (pin "2") (pinfunction "2_2") (pintype "passive"))
      (node (ref "UNIT3") (pin "18") (pinfunction "(MISO)PB6_18") (pintype "bidirectional"))
    )
    (net (code "60") (name "Net-(UNIT3-(MOSI)PB5)") (class "Default")
      (node (ref "R43") (pin "2") (pinfunction "2_2") (pintype "passive"))
      (node (ref "UNIT3") (pin "17") (pinfunction "(MOSI)PB5_17") (pintype "bidirectional"))
    )
    (net (code "61") (name "Net-(UNIT3-(OC0A)PB2)") (class "Default")
      (node (ref "R46") (pin "2") (pinfunction "2_2") (pintype "passive"))
      (node (ref "UNIT3") (pin "14") (pinfunction "(OC0A)PB2_14") (pintype "bidirectional"))
    )
    (net (code "62") (name "Net-(UNIT3-(OC1A)PB3)") (class "Default")
      (node (ref "R45") (pin "2") (pinfunction "2_2") (pintype "passive"))
      (node (ref "UNIT3") (pin "15") (pinfunction "(OC1A)PB3_15") (pintype "bidirectional"))
    )
    (net (code "63") (name "Net-(UNIT3-(OC1B)PB4)") (class "Default")
      (node (ref "R44") (pin "2") (pinfunction "2_2") (pintype "passive"))
      (node (ref "UNIT3") (pin "16") (pinfunction "(OC1B)PB4_16") (pintype "bidirectional"))
    )
    (net (code "64") (name "Net-(UNIT3-(RXD)PD0)") (class "Default")
      (node (ref "R49") (pin "1") (pinfunction "1_1") (pintype "passive"))
      (node (ref "UNIT3") (pin "2") (pinfunction "(RXD)PD0_2") (pintype "bidirectional"))
    )
    (net (code "65") (name "Net-(UNIT3-(TXD)PD1)") (class "Default")
      (node (ref "R50") (pin "1") (pinfunction "1_1") (pintype "passive"))
      (node (ref "UNIT3") (pin "3") (pinfunction "(TXD)PD1_3") (pintype "bidirectional"))
    )
    (net (code "66") (name "Net-(UNIT3-(UCSK)PB7)") (class "Default")
      (node (ref "R41") (pin "2") (pinfunction "2_2") (pintype "passive"))
      (node (ref "UNIT3") (pin "19") (pinfunction "(UCSK)PB7_19") (pintype "bidirectional"))
    )
    (net (code "67") (name "Net-(UNIT3-PA2({slash}RESET))") (class "Default")
      (node (ref "R40") (pin "1") (pinfunction "1_1") (pintype "passive"))
      (node (ref "UNIT3") (pin "1") (pinfunction "PA2(/RESET)_1") (pintype "input"))
    )
    (net (code "68") (name "Net-(UNIT4-(AIN0)PB0)") (class "Default")
      (node (ref "R61") (pin "2") (pinfunction "2_2") (pintype "passive"))
      (node (ref "UNIT4") (pin "12") (pinfunction "(AIN0)PB0_12") (pintype "bidirectional"))
    )
    (net (code "69") (name "Net-(UNIT4-(AIN1)PB1)") (class "Default")
      (node (ref "R60") (pin "2") (pinfunction "2_2") (pintype "passive"))
      (node (ref "UNIT4") (pin "13") (pinfunction "(AIN1)PB1_13") (pintype "bidirectional"))
    )
    (net (code "70") (name "Net-(UNIT4-(INT0)PD2)") (class "Default")
      (node (ref "R64") (pin "1") (pinfunction "1_1") (pintype "passive"))
      (node (ref "UNIT4") (pin "6") (pinfunction "(INT0)PD2_6") (pintype "bidirectional"))
    )
    (net (code "71") (name "Net-(UNIT4-(INT1)PD3)") (class "Default")
      (node (ref "R65") (pin "1") (pinfunction "1_1") (pintype "passive"))
      (node (ref "UNIT4") (pin "7") (pinfunction "(INT1)PD3_7") (pintype "bidirectional"))
    )
    (net (code "72") (name "Net-(UNIT4-(MISO)PB6)") (class "Default")
      (node (ref "R55") (pin "2") (pinfunction "2_2") (pintype "passive"))
      (node (ref "UNIT4") (pin "18") (pinfunction "(MISO)PB6_18") (pintype "bidirectional"))
    )
    (net (code "73") (name "Net-(UNIT4-(MOSI)PB5)") (class "Default")
      (node (ref "R56") (pin "2") (pinfunction "2_2") (pintype "passive"))
      (node (ref "UNIT4") (pin "17") (pinfunction "(MOSI)PB5_17") (pintype "bidirectional"))
    )
    (net (code "74") (name "Net-(UNIT4-(OC0A)PB2)") (class "Default")
      (node (ref "R59") (pin "2") (pinfunction "2_2") (pintype "passive"))
      (node (ref "UNIT4") (pin "14") (pinfunction "(OC0A)PB2_14") (pintype "bidirectional"))
    )
    (net (code "75") (name "Net-(UNIT4-(OC1A)PB3)") (class "Default")
      (node (ref "R58") (pin "2") (pinfunction "2_2") (pintype "passive"))
      (node (ref "UNIT4") (pin "15") (pinfunction "(OC1A)PB3_15") (pintype "bidirectional"))
    )
    (net (code "76") (name "Net-(UNIT4-(OC1B)PB4)") (class "Default")
      (node (ref "R57") (pin "2") (pinfunction "2_2") (pintype "passive"))
      (node (ref "UNIT4") (pin "16") (pinfunction "(OC1B)PB4_16") (pintype "bidirectional"))
    )
    (net (code "77") (name "Net-(UNIT4-(RXD)PD0)") (class "Default")
      (node (ref "R62") (pin "1") (pinfunction "1_1") (pintype "passive"))
      (node (ref "UNIT4") (pin "2") (pinfunction "(RXD)PD0_2") (pintype "bidirectional"))
    )
    (net (code "78") (name "Net-(UNIT4-(TXD)PD1)") (class "Default")
      (node (ref "R63") (pin "1") (pinfunction "1_1") (pintype "passive"))
      (node (ref "UNIT4") (pin "3") (pinfunction "(TXD)PD1_3") (pintype "bidirectional"))
    )
    (net (code "79") (name "Net-(UNIT4-(UCSK)PB7)") (class "Default")
      (node (ref "R54") (pin "2") (pinfunction "2_2") (pintype "passive"))
      (node (ref "UNIT4") (pin "19") (pinfunction "(UCSK)PB7_19") (pintype "bidirectional"))
    )
    (net (code "80") (name "Net-(UNIT4-PA2({slash}RESET))") (class "Default")
      (node (ref "R53") (pin "1") (pinfunction "1_1") (pintype "passive"))
      (node (ref "UNIT4") (pin "1") (pinfunction "PA2(/RESET)_1") (pintype "input"))
    )
    (net (code "81") (name "Net-(UNIT5-(AIN0)PB0)") (class "Default")
      (node (ref "R74") (pin "2") (pinfunction "2_2") (pintype "passive"))
      (node (ref "UNIT5") (pin "12") (pinfunction "(AIN0)PB0_12") (pintype "bidirectional"))
    )
    (net (code "82") (name "Net-(UNIT5-(AIN1)PB1)") (class "Default")
      (node (ref "R73") (pin "2") (pinfunction "2_2") (pintype "passive"))
      (node (ref "UNIT5") (pin "13") (pinfunction "(AIN1)PB1_13") (pintype "bidirectional"))
    )
    (net (code "83") (name "Net-(UNIT5-(INT0)PD2)") (class "Default")
      (node (ref "R77") (pin "1") (pinfunction "1_1") (pintype "passive"))
      (node (ref "UNIT5") (pin "6") (pinfunction "(INT0)PD2_6") (pintype "bidirectional"))
    )
    (net (code "84") (name "Net-(UNIT5-(INT1)PD3)") (class "Default")
      (node (ref "R78") (pin "1") (pinfunction "1_1") (pintype "passive"))
      (node (ref "UNIT5") (pin "7") (pinfunction "(INT1)PD3_7") (pintype "bidirectional"))
    )
    (net (code "85") (name "Net-(UNIT5-(MISO)PB6)") (class "Default")
      (node (ref "R68") (pin "2") (pinfunction "2_2") (pintype "passive"))
      (node (ref "UNIT5") (pin "18") (pinfunction "(MISO)PB6_18") (pintype "bidirectional"))
    )
    (net (code "86") (name "Net-(UNIT5-(MOSI)PB5)") (class "Default")
      (node (ref "R69") (pin "2") (pinfunction "2_2") (pintype "passive"))
      (node (ref "UNIT5") (pin "17") (pinfunction "(MOSI)PB5_17") (pintype "bidirectional"))
    )
    (net (code "87") (name "Net-(UNIT5-(OC0A)PB2)") (class "Default")
      (node (ref "R72") (pin "2") (pinfunction "2_2") (pintype "passive"))
      (node (ref "UNIT5") (pin "14") (pinfunction "(OC0A)PB2_14") (pintype "bidirectional"))
    )
    (net (code "88") (name "Net-(UNIT5-(OC1A)PB3)") (class "Default")
      (node (ref "R71") (pin "2") (pinfunction "2_2") (pintype "passive"))
      (node (ref "UNIT5") (pin "15") (pinfunction "(OC1A)PB3_15") (pintype "bidirectional"))
    )
    (net (code "89") (name "Net-(UNIT5-(OC1B)PB4)") (class "Default")
      (node (ref "R70") (pin "2") (pinfunction "2_2") (pintype "passive"))
      (node (ref "UNIT5") (pin "16") (pinfunction "(OC1B)PB4_16") (pintype "bidirectional"))
    )
    (net (code "90") (name "Net-(UNIT5-(RXD)PD0)") (class "Default")
      (node (ref "R75") (pin "1") (pinfunction "1_1") (pintype "passive"))
      (node (ref "UNIT5") (pin "2") (pinfunction "(RXD)PD0_2") (pintype "bidirectional"))
    )
    (net (code "91") (name "Net-(UNIT5-(TXD)PD1)") (class "Default")
      (node (ref "R76") (pin "1") (pinfunction "1_1") (pintype "passive"))
      (node (ref "UNIT5") (pin "3") (pinfunction "(TXD)PD1_3") (pintype "bidirectional"))
    )
    (net (code "92") (name "Net-(UNIT5-(UCSK)PB7)") (class "Default")
      (node (ref "R67") (pin "2") (pinfunction "2_2") (pintype "passive"))
      (node (ref "UNIT5") (pin "19") (pinfunction "(UCSK)PB7_19") (pintype "bidirectional"))
    )
    (net (code "93") (name "Net-(UNIT5-PA2({slash}RESET))") (class "Default")
      (node (ref "R66") (pin "1") (pinfunction "1_1") (pintype "passive"))
      (node (ref "UNIT5") (pin "1") (pinfunction "PA2(/RESET)_1") (pintype "input"))
    )
    (net (code "94") (name "Net-(UNIT6-(AIN0)PB0)") (class "Default")
      (node (ref "R87") (pin "2") (pinfunction "2_2") (pintype "passive"))
      (node (ref "UNIT6") (pin "12") (pinfunction "(AIN0)PB0_12") (pintype "bidirectional"))
    )
    (net (code "95") (name "Net-(UNIT6-(AIN1)PB1)") (class "Default")
      (node (ref "R86") (pin "2") (pinfunction "2_2") (pintype "passive"))
      (node (ref "UNIT6") (pin "13") (pinfunction "(AIN1)PB1_13") (pintype "bidirectional"))
    )
    (net (code "96") (name "Net-(UNIT6-(INT0)PD2)") (class "Default")
      (node (ref "R90") (pin "1") (pinfunction "1_1") (pintype "passive"))
      (node (ref "UNIT6") (pin "6") (pinfunction "(INT0)PD2_6") (pintype "bidirectional"))
    )
    (net (code "97") (name "Net-(UNIT6-(INT1)PD3)") (class "Default")
      (node (ref "R91") (pin "1") (pinfunction "1_1") (pintype "passive"))
      (node (ref "UNIT6") (pin "7") (pinfunction "(INT1)PD3_7") (pintype "bidirectional"))
    )
    (net (code "98") (name "Net-(UNIT6-(MISO)PB6)") (class "Default")
      (node (ref "R81") (pin "2") (pinfunction "2_2") (pintype "passive"))
      (node (ref "UNIT6") (pin "18") (pinfunction "(MISO)PB6_18") (pintype "bidirectional"))
    )
    (net (code "99") (name "Net-(UNIT6-(MOSI)PB5)") (class "Default")
      (node (ref "R82") (pin "2") (pinfunction "2_2") (pintype "passive"))
      (node (ref "UNIT6") (pin "17") (pinfunction "(MOSI)PB5_17") (pintype "bidirectional"))
    )
    (net (code "100") (name "Net-(UNIT6-(OC0A)PB2)") (class "Default")
      (node (ref "R85") (pin "2") (pinfunction "2_2") (pintype "passive"))
      (node (ref "UNIT6") (pin "14") (pinfunction "(OC0A)PB2_14") (pintype "bidirectional"))
    )
    (net (code "101") (name "Net-(UNIT6-(OC1A)PB3)") (class "Default")
      (node (ref "R84") (pin "2") (pinfunction "2_2") (pintype "passive"))
      (node (ref "UNIT6") (pin "15") (pinfunction "(OC1A)PB3_15") (pintype "bidirectional"))
    )
    (net (code "102") (name "Net-(UNIT6-(OC1B)PB4)") (class "Default")
      (node (ref "R83") (pin "2") (pinfunction "2_2") (pintype "passive"))
      (node (ref "UNIT6") (pin "16") (pinfunction "(OC1B)PB4_16") (pintype "bidirectional"))
    )
    (net (code "103") (name "Net-(UNIT6-(RXD)PD0)") (class "Default")
      (node (ref "R88") (pin "1") (pinfunction "1_1") (pintype "passive"))
      (node (ref "UNIT6") (pin "2") (pinfunction "(RXD)PD0_2") (pintype "bidirectional"))
    )
    (net (code "104") (name "Net-(UNIT6-(TXD)PD1)") (class "Default")
      (node (ref "R89") (pin "1") (pinfunction "1_1") (pintype "passive"))
      (node (ref "UNIT6") (pin "3") (pinfunction "(TXD)PD1_3") (pintype "bidirectional"))
    )
    (net (code "105") (name "Net-(UNIT6-(UCSK)PB7)") (class "Default")
      (node (ref "R80") (pin "2") (pinfunction "2_2") (pintype "passive"))
      (node (ref "UNIT6") (pin "19") (pinfunction "(UCSK)PB7_19") (pintype "bidirectional"))
    )
    (net (code "106") (name "Net-(UNIT6-PA2({slash}RESET))") (class "Default")
      (node (ref "R79") (pin "1") (pinfunction "1_1") (pintype "passive"))
      (node (ref "UNIT6") (pin "1") (pinfunction "PA2(/RESET)_1") (pintype "input"))
    )
    (net (code "107") (name "Net-(UNIT7-(AIN0)PB0)") (class "Default")
      (node (ref "R100") (pin "2") (pinfunction "2_2") (pintype "passive"))
      (node (ref "UNIT7") (pin "12") (pinfunction "(AIN0)PB0_12") (pintype "bidirectional"))
    )
    (net (code "108") (name "Net-(UNIT7-(AIN1)PB1)") (class "Default")
      (node (ref "R99") (pin "2") (pinfunction "2_2") (pintype "passive"))
      (node (ref "UNIT7") (pin "13") (pinfunction "(AIN1)PB1_13") (pintype "bidirectional"))
    )
    (net (code "109") (name "Net-(UNIT7-(INT0)PD2)") (class "Default")
      (node (ref "R103") (pin "1") (pinfunction "1_1") (pintype "passive"))
      (node (ref "UNIT7") (pin "6") (pinfunction "(INT0)PD2_6") (pintype "bidirectional"))
    )
    (net (code "110") (name "Net-(UNIT7-(INT1)PD3)") (class "Default")
      (node (ref "R104") (pin "1") (pinfunction "1_1") (pintype "passive"))
      (node (ref "UNIT7") (pin "7") (pinfunction "(INT1)PD3_7") (pintype "bidirectional"))
    )
    (net (code "111") (name "Net-(UNIT7-(MISO)PB6)") (class "Default")
      (node (ref "R94") (pin "2") (pinfunction "2_2") (pintype "passive"))
      (node (ref "UNIT7") (pin "18") (pinfunction "(MISO)PB6_18") (pintype "bidirectional"))
    )
    (net (code "112") (name "Net-(UNIT7-(MOSI)PB5)") (class "Default")
      (node (ref "R95") (pin "2") (pinfunction "2_2") (pintype "passive"))
      (node (ref "UNIT7") (pin "17") (pinfunction "(MOSI)PB5_17") (pintype "bidirectional"))
    )
    (net (code "113") (name "Net-(UNIT7-(OC0A)PB2)") (class "Default")
      (node (ref "R98") (pin "2") (pinfunction "2_2") (pintype "passive"))
      (node (ref "UNIT7") (pin "14") (pinfunction "(OC0A)PB2_14") (pintype "bidirectional"))
    )
    (net (code "114") (name "Net-(UNIT7-(OC1A)PB3)") (class "Default")
      (node (ref "R97") (pin "2") (pinfunction "2_2") (pintype "passive"))
      (node (ref "UNIT7") (pin "15") (pinfunction "(OC1A)PB3_15") (pintype "bidirectional"))
    )
    (net (code "115") (name "Net-(UNIT7-(OC1B)PB4)") (class "Default")
      (node (ref "R96") (pin "2") (pinfunction "2_2") (pintype "passive"))
      (node (ref "UNIT7") (pin "16") (pinfunction "(OC1B)PB4_16") (pintype "bidirectional"))
    )
    (net (code "116") (name "Net-(UNIT7-(RXD)PD0)") (class "Default")
      (node (ref "R101") (pin "1") (pinfunction "1_1") (pintype "passive"))
      (node (ref "UNIT7") (pin "2") (pinfunction "(RXD)PD0_2") (pintype "bidirectional"))
    )
    (net (code "117") (name "Net-(UNIT7-(TXD)PD1)") (class "Default")
      (node (ref "R102") (pin "1") (pinfunction "1_1") (pintype "passive"))
      (node (ref "UNIT7") (pin "3") (pinfunction "(TXD)PD1_3") (pintype "bidirectional"))
    )
    (net (code "118") (name "Net-(UNIT7-(UCSK)PB7)") (class "Default")
      (node (ref "R93") (pin "2") (pinfunction "2_2") (pintype "passive"))
      (node (ref "UNIT7") (pin "19") (pinfunction "(UCSK)PB7_19") (pintype "bidirectional"))
    )
    (net (code "119") (name "Net-(UNIT7-PA2({slash}RESET))") (class "Default")
      (node (ref "R92") (pin "1") (pinfunction "1_1") (pintype "passive"))
      (node (ref "UNIT7") (pin "1") (pinfunction "PA2(/RESET)_1") (pintype "input"))
    )
    (net (code "120") (name "VCC") (class "Default")
      (node (ref "JP2") (pin "1") (pinfunction "1_1") (pintype "passive"))
      (node (ref "R10") (pin "2") (pinfunction "2_2") (pintype "passive"))
      (node (ref "R27") (pin "2") (pinfunction "2_2") (pintype "passive"))
      (node (ref "R40") (pin "2") (pinfunction "2_2") (pintype "passive"))
      (node (ref "R5") (pin "2") (pinfunction "2_2") (pintype "passive"))
      (node (ref "R53") (pin "2") (pinfunction "2_2") (pintype "passive"))
      (node (ref "R66") (pin "2") (pinfunction "2_2") (pintype "passive"))
      (node (ref "R79") (pin "2") (pinfunction "2_2") (pintype "passive"))
      (node (ref "R92") (pin "2") (pinfunction "2_2") (pintype "passive"))
      (node (ref "SJ1") (pin "1") (pinfunction "1_1") (pintype "passive"))
      (node (ref "UNIT0") (pin "20") (pinfunction "VCC_20") (pintype "power_in"))
      (node (ref "UNIT1") (pin "20") (pinfunction "VCC_20") (pintype "power_in"))
      (node (ref "UNIT1") (pin "8") (pinfunction "(T0)PD4_8") (pintype "bidirectional"))
      (node (ref "UNIT2") (pin "20") (pinfunction "VCC_20") (pintype "power_in"))
      (node (ref "UNIT2") (pin "9") (pinfunction "(T1)PD5_9") (pintype "bidirectional"))
      (node (ref "UNIT3") (pin "20") (pinfunction "VCC_20") (pintype "power_in"))
      (node (ref "UNIT3") (pin "8") (pinfunction "(T0)PD4_8") (pintype "bidirectional"))
      (node (ref "UNIT3") (pin "9") (pinfunction "(T1)PD5_9") (pintype "bidirectional"))
      (node (ref "UNIT4") (pin "11") (pinfunction "(ICP)PD6_11") (pintype "bidirectional"))
      (node (ref "UNIT4") (pin "20") (pinfunction "VCC_20") (pintype "power_in"))
      (node (ref "UNIT5") (pin "11") (pinfunction "(ICP)PD6_11") (pintype "bidirectional"))
      (node (ref "UNIT5") (pin "20") (pinfunction "VCC_20") (pintype "power_in"))
      (node (ref "UNIT5") (pin "8") (pinfunction "(T0)PD4_8") (pintype "bidirectional"))
      (node (ref "UNIT6") (pin "11") (pinfunction "(ICP)PD6_11") (pintype "bidirectional"))
      (node (ref "UNIT6") (pin "20") (pinfunction "VCC_20") (pintype "power_in"))
      (node (ref "UNIT6") (pin "9") (pinfunction "(T1)PD5_9") (pintype "bidirectional"))
      (node (ref "UNIT7") (pin "11") (pinfunction "(ICP)PD6_11") (pintype "bidirectional"))
      (node (ref "UNIT7") (pin "20") (pinfunction "VCC_20") (pintype "power_in"))
      (node (ref "UNIT7") (pin "8") (pinfunction "(T0)PD4_8") (pintype "bidirectional"))
      (node (ref "UNIT7") (pin "9") (pinfunction "(T1)PD5_9") (pintype "bidirectional"))
    )
  )
)
